# Main.net
KiCad netlist of a schematic drawn in Altium Designer
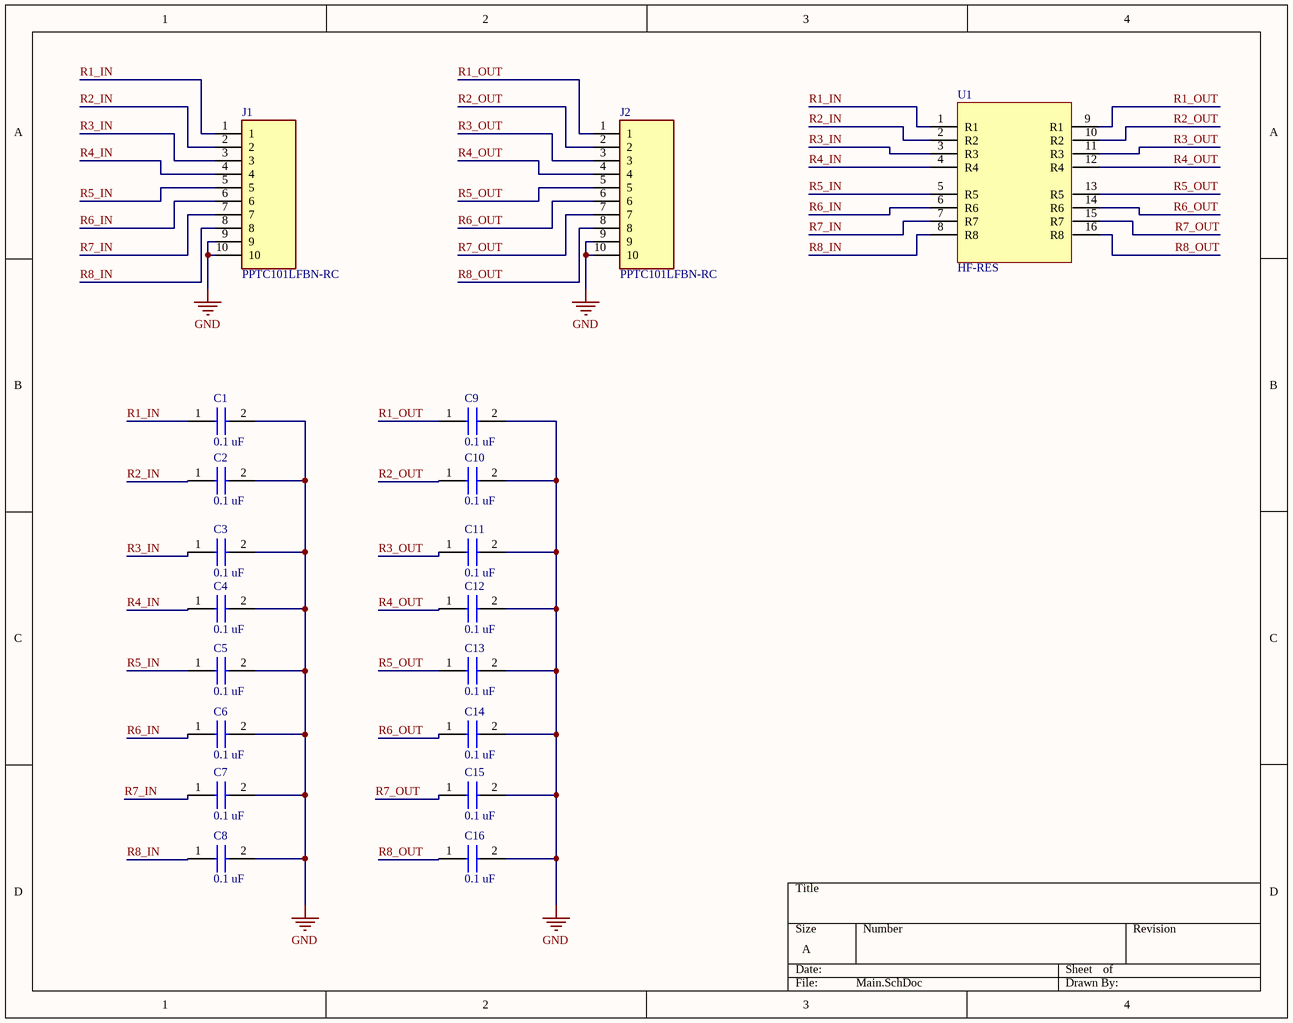
[diagram p0: Main.SchDoc]

(export (version "E")
  (design (tool "Eeschema 10.0.6"))
  (components
    (comp (ref "C1")
      (value "0.1 uF")
      (footprint "Packaging:C0603")
      (description "Capacitor")
      (fields
        (field (name "MANUFACTURER_PART_NUMBER") "C0603C104K5RAC7411")
        (field (name "MOUSER PART NUMBER") "80-C0603C104K5R7411")
      )
      (libsource (lib "Packaging") (part "C0603C104K5RAC7411"))
    )
    (comp (ref "C2")
      (value "0.1 uF")
      (footprint "Packaging:C0603")
      (description "Capacitor")
      (fields
        (field (name "MANUFACTURER_PART_NUMBER") "C0603C104K5RAC7411")
        (field (name "MOUSER PART NUMBER") "80-C0603C104K5R7411")
      )
      (libsource (lib "Packaging") (part "C0603C104K5RAC7411"))
    )
    (comp (ref "C3")
      (value "0.1 uF")
      (footprint "Packaging:C0603")
      (description "Capacitor")
      (fields
        (field (name "MANUFACTURER_PART_NUMBER") "C0603C104K5RAC7411")
        (field (name "MOUSER PART NUMBER") "80-C0603C104K5R7411")
      )
      (libsource (lib "Packaging") (part "C0603C104K5RAC7411"))
    )
    (comp (ref "C4")
      (value "0.1 uF")
      (footprint "Packaging:C0603")
      (description "Capacitor")
      (fields
        (field (name "MANUFACTURER_PART_NUMBER") "C0603C104K5RAC7411")
        (field (name "MOUSER PART NUMBER") "80-C0603C104K5R7411")
      )
      (libsource (lib "Packaging") (part "C0603C104K5RAC7411"))
    )
    (comp (ref "C5")
      (value "0.1 uF")
      (footprint "Packaging:C0603")
      (description "Capacitor")
      (fields
        (field (name "MANUFACTURER_PART_NUMBER") "C0603C104K5RAC7411")
        (field (name "MOUSER PART NUMBER") "80-C0603C104K5R7411")
      )
      (libsource (lib "Packaging") (part "C0603C104K5RAC7411"))
    )
    (comp (ref "C6")
      (value "0.1 uF")
      (footprint "Packaging:C0603")
      (description "Capacitor")
      (fields
        (field (name "MANUFACTURER_PART_NUMBER") "C0603C104K5RAC7411")
        (field (name "MOUSER PART NUMBER") "80-C0603C104K5R7411")
      )
      (libsource (lib "Packaging") (part "C0603C104K5RAC7411"))
    )
    (comp (ref "C7")
      (value "0.1 uF")
      (footprint "Packaging:C0603")
      (description "Capacitor")
      (fields
        (field (name "MANUFACTURER_PART_NUMBER") "C0603C104K5RAC7411")
        (field (name "MOUSER PART NUMBER") "80-C0603C104K5R7411")
      )
      (libsource (lib "Packaging") (part "C0603C104K5RAC7411"))
    )
    (comp (ref "C8")
      (value "0.1 uF")
      (footprint "Packaging:C0603")
      (description "Capacitor")
      (fields
        (field (name "MANUFACTURER_PART_NUMBER") "C0603C104K5RAC7411")
        (field (name "MOUSER PART NUMBER") "80-C0603C104K5R7411")
      )
      (libsource (lib "Packaging") (part "C0603C104K5RAC7411"))
    )
    (comp (ref "C9")
      (value "0.1 uF")
      (footprint "Packaging:C0603")
      (description "Capacitor")
      (fields
        (field (name "MANUFACTURER_PART_NUMBER") "C0603C104K5RAC7411")
        (field (name "MOUSER PART NUMBER") "80-C0603C104K5R7411")
      )
      (libsource (lib "Packaging") (part "C0603C104K5RAC7411"))
    )
    (comp (ref "C10")
      (value "0.1 uF")
      (footprint "Packaging:C0603")
      (description "Capacitor")
      (fields
        (field (name "MANUFACTURER_PART_NUMBER") "C0603C104K5RAC7411")
        (field (name "MOUSER PART NUMBER") "80-C0603C104K5R7411")
      )
      (libsource (lib "Packaging") (part "C0603C104K5RAC7411"))
    )
    (comp (ref "C11")
      (value "0.1 uF")
      (footprint "Packaging:C0603")
      (description "Capacitor")
      (fields
        (field (name "MANUFACTURER_PART_NUMBER") "C0603C104K5RAC7411")
        (field (name "MOUSER PART NUMBER") "80-C0603C104K5R7411")
      )
      (libsource (lib "Packaging") (part "C0603C104K5RAC7411"))
    )
    (comp (ref "C12")
      (value "0.1 uF")
      (footprint "Packaging:C0603")
      (description "Capacitor")
      (fields
        (field (name "MANUFACTURER_PART_NUMBER") "C0603C104K5RAC7411")
        (field (name "MOUSER PART NUMBER") "80-C0603C104K5R7411")
      )
      (libsource (lib "Packaging") (part "C0603C104K5RAC7411"))
    )
    (comp (ref "C13")
      (value "0.1 uF")
      (footprint "Packaging:C0603")
      (description "Capacitor")
      (fields
        (field (name "MANUFACTURER_PART_NUMBER") "C0603C104K5RAC7411")
        (field (name "MOUSER PART NUMBER") "80-C0603C104K5R7411")
      )
      (libsource (lib "Packaging") (part "C0603C104K5RAC7411"))
    )
    (comp (ref "C14")
      (value "0.1 uF")
      (footprint "Packaging:C0603")
      (description "Capacitor")
      (fields
        (field (name "MANUFACTURER_PART_NUMBER") "C0603C104K5RAC7411")
        (field (name "MOUSER PART NUMBER") "80-C0603C104K5R7411")
      )
      (libsource (lib "Packaging") (part "C0603C104K5RAC7411"))
    )
    (comp (ref "C15")
      (value "0.1 uF")
      (footprint "Packaging:C0603")
      (description "Capacitor")
      (fields
        (field (name "MANUFACTURER_PART_NUMBER") "C0603C104K5RAC7411")
        (field (name "MOUSER PART NUMBER") "80-C0603C104K5R7411")
      )
      (libsource (lib "Packaging") (part "C0603C104K5RAC7411"))
    )
    (comp (ref "C16")
      (value "0.1 uF")
      (footprint "Packaging:C0603")
      (description "Capacitor")
      (fields
        (field (name "MANUFACTURER_PART_NUMBER") "C0603C104K5RAC7411")
        (field (name "MOUSER PART NUMBER") "80-C0603C104K5R7411")
      )
      (libsource (lib "Packaging") (part "C0603C104K5RAC7411"))
    )
    (comp (ref "J1")
      (value "PPTC101LFBN-RC")
      (footprint "Packaging:RHDR10W80P0X254_1X10_2590X254X850P")
      (description "Connector")
      (libsource (lib "Packaging") (part "PPTC101LFBN-RC"))
    )
    (comp (ref "J2")
      (value "PPTC101LFBN-RC")
      (footprint "Packaging:RHDR10W80P0X254_1X10_2590X254X850P")
      (description "Connector")
      (libsource (lib "Packaging") (part "PPTC101LFBN-RC"))
    )
    (comp (ref "U1")
      (value "HF-RES")
      (footprint "Packaging:HF-COB")
      (description "Resistor chip for packaging test")
      (libsource (lib "Packaging") (part "HF-RES"))
    )
  )
  (nets
    (net (code "1") (name "/R1_IN") (class "Default")
      (node (ref "C1") (pin "1") (pinfunction "1_1") (pintype "passive"))
      (node (ref "J1") (pin "1") (pinfunction "1_1") (pintype "passive"))
      (node (ref "U1") (pin "1") (pinfunction "R1_1") (pintype "passive"))
    )
    (net (code "2") (name "/R1_OUT") (class "Default")
      (node (ref "C9") (pin "1") (pinfunction "1_1") (pintype "passive"))
      (node (ref "J2") (pin "1") (pinfunction "1_1") (pintype "passive"))
      (node (ref "U1") (pin "9") (pinfunction "R1_9") (pintype "passive"))
    )
    (net (code "3") (name "/R2_IN") (class "Default")
      (node (ref "C2") (pin "1") (pinfunction "1_1") (pintype "passive"))
      (node (ref "J1") (pin "2") (pinfunction "2_2") (pintype "passive"))
      (node (ref "U1") (pin "2") (pinfunction "R2_2") (pintype "passive"))
    )
    (net (code "4") (name "/R2_OUT") (class "Default")
      (node (ref "C10") (pin "1") (pinfunction "1_1") (pintype "passive"))
      (node (ref "J2") (pin "2") (pinfunction "2_2") (pintype "passive"))
      (node (ref "U1") (pin "10") (pinfunction "R2_10") (pintype "passive"))
    )
    (net (code "5") (name "/R3_IN") (class "Default")
      (node (ref "C3") (pin "1") (pinfunction "1_1") (pintype "passive"))
      (node (ref "J1") (pin "3") (pinfunction "3_3") (pintype "passive"))
      (node (ref "U1") (pin "3") (pinfunction "R3_3") (pintype "passive"))
    )
    (net (code "6") (name "/R3_OUT") (class "Default")
      (node (ref "C11") (pin "1") (pinfunction "1_1") (pintype "passive"))
      (node (ref "J2") (pin "3") (pinfunction "3_3") (pintype "passive"))
      (node (ref "U1") (pin "11") (pinfunction "R3_11") (pintype "passive"))
    )
    (net (code "7") (name "/R4_IN") (class "Default")
      (node (ref "C4") (pin "1") (pinfunction "1_1") (pintype "passive"))
      (node (ref "J1") (pin "4") (pinfunction "4_4") (pintype "passive"))
      (node (ref "U1") (pin "4") (pinfunction "R4_4") (pintype "passive"))
    )
    (net (code "8") (name "/R4_OUT") (class "Default")
      (node (ref "C12") (pin "1") (pinfunction "1_1") (pintype "passive"))
      (node (ref "J2") (pin "4") (pinfunction "4_4") (pintype "passive"))
      (node (ref "U1") (pin "12") (pinfunction "R4_12") (pintype "passive"))
    )
    (net (code "9") (name "/R5_IN") (class "Default")
      (node (ref "C5") (pin "1") (pinfunction "1_1") (pintype "passive"))
      (node (ref "J1") (pin "5") (pinfunction "5_5") (pintype "passive"))
      (node (ref "U1") (pin "5") (pinfunction "R5_5") (pintype "passive"))
    )
    (net (code "10") (name "/R5_OUT") (class "Default")
      (node (ref "C13") (pin "1") (pinfunction "1_1") (pintype "passive"))
      (node (ref "J2") (pin "5") (pinfunction "5_5") (pintype "passive"))
      (node (ref "U1") (pin "13") (pinfunction "R5_13") (pintype "passive"))
    )
    (net (code "11") (name "/R6_IN") (class "Default")
      (node (ref "C6") (pin "1") (pinfunction "1_1") (pintype "passive"))
      (node (ref "J1") (pin "6") (pinfunction "6_6") (pintype "passive"))
      (node (ref "U1") (pin "6") (pinfunction "R6_6") (pintype "passive"))
    )
    (net (code "12") (name "/R6_OUT") (class "Default")
      (node (ref "C14") (pin "1") (pinfunction "1_1") (pintype "passive"))
      (node (ref "J2") (pin "6") (pinfunction "6_6") (pintype "passive"))
      (node (ref "U1") (pin "14") (pinfunction "R6_14") (pintype "passive"))
    )
    (net (code "13") (name "/R7_IN") (class "Default")
      (node (ref "C7") (pin "1") (pinfunction "1_1") (pintype "passive"))
      (node (ref "J1") (pin "7") (pinfunction "7_7") (pintype "passive"))
      (node (ref "U1") (pin "7") (pinfunction "R7_7") (pintype "passive"))
    )
    (net (code "14") (name "/R7_OUT") (class "Default")
      (node (ref "C15") (pin "1") (pinfunction "1_1") (pintype "passive"))
      (node (ref "J2") (pin "7") (pinfunction "7_7") (pintype "passive"))
      (node (ref "U1") (pin "15") (pinfunction "R7_15") (pintype "passive"))
    )
    (net (code "15") (name "/R8_IN") (class "Default")
      (node (ref "C8") (pin "1") (pinfunction "1_1") (pintype "passive"))
      (node (ref "J1") (pin "8") (pinfunction "8_8") (pintype "passive"))
      (node (ref "U1") (pin "8") (pinfunction "R8_8") (pintype "passive"))
    )
    (net (code "16") (name "/R8_OUT") (class "Default")
      (node (ref "C16") (pin "1") (pinfunction "1_1") (pintype "passive"))
      (node (ref "J2") (pin "8") (pinfunction "8_8") (pintype "passive"))
      (node (ref "U1") (pin "16") (pinfunction "R8_16") (pintype "passive"))
    )
    (net (code "17") (name "GND") (class "Default")
      (node (ref "C1") (pin "2") (pinfunction "2_2") (pintype "passive"))
      (node (ref "C10") (pin "2") (pinfunction "2_2") (pintype "passive"))
      (node (ref "C11") (pin "2") (pinfunction "2_2") (pintype "passive"))
      (node (ref "C12") (pin "2") (pinfunction "2_2") (pintype "passive"))
      (node (ref "C13") (pin "2") (pinfunction "2_2") (pintype "passive"))
      (node (ref "C14") (pin "2") (pinfunction "2_2") (pintype "passive"))
      (node (ref "C15") (pin "2") (pinfunction "2_2") (pintype "passive"))
      (node (ref "C16") (pin "2") (pinfunction "2_2") (pintype "passive"))
      (node (ref "C2") (pin "2") (pinfunction "2_2") (pintype "passive"))
      (node (ref "C3") (pin "2") (pinfunction "2_2") (pintype "passive"))
      (node (ref "C4") (pin "2") (pinfunction "2_2") (pintype "passive"))
      (node (ref "C5") (pin "2") (pinfunction "2_2") (pintype "passive"))
      (node (ref "C6") (pin "2") (pinfunction "2_2") (pintype "passive"))
      (node (ref "C7") (pin "2") (pinfunction "2_2") (pintype "passive"))
      (node (ref "C8") (pin "2") (pinfunction "2_2") (pintype "passive"))
      (node (ref "C9") (pin "2") (pinfunction "2_2") (pintype "passive"))
      (node (ref "J1") (pin "10") (pinfunction "10_10") (pintype "passive"))
      (node (ref "J1") (pin "9") (pinfunction "9_9") (pintype "passive"))
      (node (ref "J2") (pin "10") (pinfunction "10_10") (pintype "passive"))
      (node (ref "J2") (pin "9") (pinfunction "9_9") (pintype "passive"))
    )
  )
)
